# modeSelection.net
KiCad netlist of a schematic drawn in Altium Designer
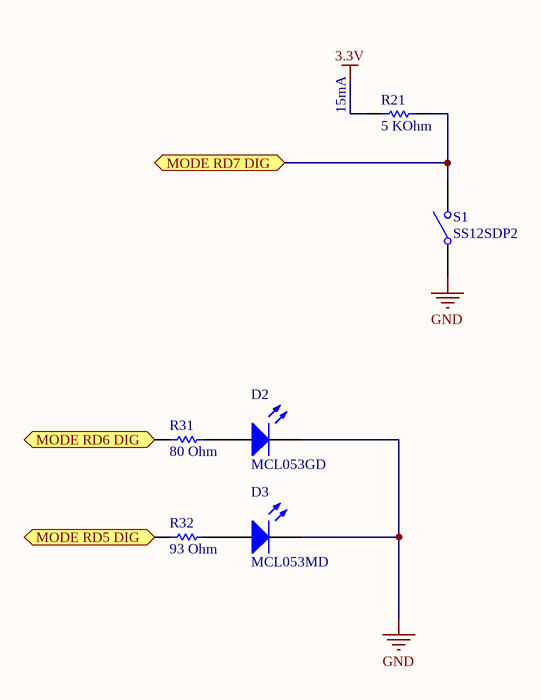
[diagram p0: modeSelection.SchDoc]

(export (version "E")
  (design (tool "Eeschema 10.0.6"))
  (components
    (comp (ref "D2")
      (value "MCL053GD")
      (footprint "LedGreen")
      (description "Typical INFRARED GaAs LED")
      (fields (field (name "PUBLISHER") "Altium Limited"))
      (libsource (lib "Miscellaneous Devices") (part "LED0"))
    )
    (comp (ref "D3")
      (value "MCL053MD")
      (footprint "LedGreen")
      (description "Typical INFRARED GaAs LED")
      (fields (field (name "PUBLISHER") "Altium Limited"))
      (libsource (lib "Miscellaneous Devices") (part "LED0"))
    )
    (comp (ref "R21")
      (value "5 KOhm")
      (footprint "Resistor0603")
      (description "Resistor")
      (fields (field (name "PUBLISHER") "Altium Limited"))
      (libsource (lib "Miscellaneous Devices") (part "Res1"))
    )
    (comp (ref "R31")
      (value "80 Ohm")
      (footprint "Resistor0603")
      (description "Resistor")
      (fields (field (name "PUBLISHER") "Altium Limited"))
      (libsource (lib "Miscellaneous Devices") (part "Res1"))
    )
    (comp (ref "R32")
      (value "93 Ohm")
      (footprint "Resistor0603")
      (description "Resistor")
      (fields (field (name "PUBLISHER") "Altium Limited"))
      (libsource (lib "Miscellaneous Devices") (part "Res1"))
    )
    (comp (ref "S1")
      (value "SS12SDP2")
      (footprint "Switch")
      (description "Single-Pole, Single-Throw Switch")
      (fields (field (name "PUBLISHER") "Altium Limited"))
      (libsource (lib "Miscellaneous Devices") (part "SW-SPST"))
    )
  )
  (nets
    (net (code "1") (name "/MODE RD5 DIG") (class "Default")
      (node (ref "R32") (pin "1") (pinfunction "1_1") (pintype "passive"))
    )
    (net (code "2") (name "/MODE RD6 DIG") (class "Default")
      (node (ref "R31") (pin "1") (pinfunction "1_1") (pintype "passive"))
    )
    (net (code "3") (name "/MODE RD7 DIG") (class "Default")
      (node (ref "R21") (pin "1") (pinfunction "1_1") (pintype "passive"))
      (node (ref "S1") (pin "2") (pinfunction "NO_2") (pintype "passive"))
    )
    (net (code "4") (name "3.3V") (class "Default")
      (node (ref "R21") (pin "2") (pinfunction "2_2") (pintype "passive"))
    )
    (net (code "5") (name "GND") (class "Default")
      (node (ref "D2") (pin "2") (pinfunction "K_2") (pintype "passive"))
      (node (ref "D3") (pin "2") (pinfunction "K_2") (pintype "passive"))
      (node (ref "S1") (pin "1") (pinfunction "COMMON_1") (pintype "passive"))
    )
    (net (code "6") (name "Net-(D2-A)") (class "Default")
      (node (ref "D2") (pin "1") (pinfunction "A_1") (pintype "passive"))
      (node (ref "R31") (pin "2") (pinfunction "2_2") (pintype "passive"))
    )
    (net (code "7") (name "Net-(D3-A)") (class "Default")
      (node (ref "D3") (pin "1") (pinfunction "A_1") (pintype "passive"))
      (node (ref "R32") (pin "2") (pinfunction "2_2") (pintype "passive"))
    )
  )
)
